# battery.net
KiCad netlist of a schematic drawn in Altium Designer
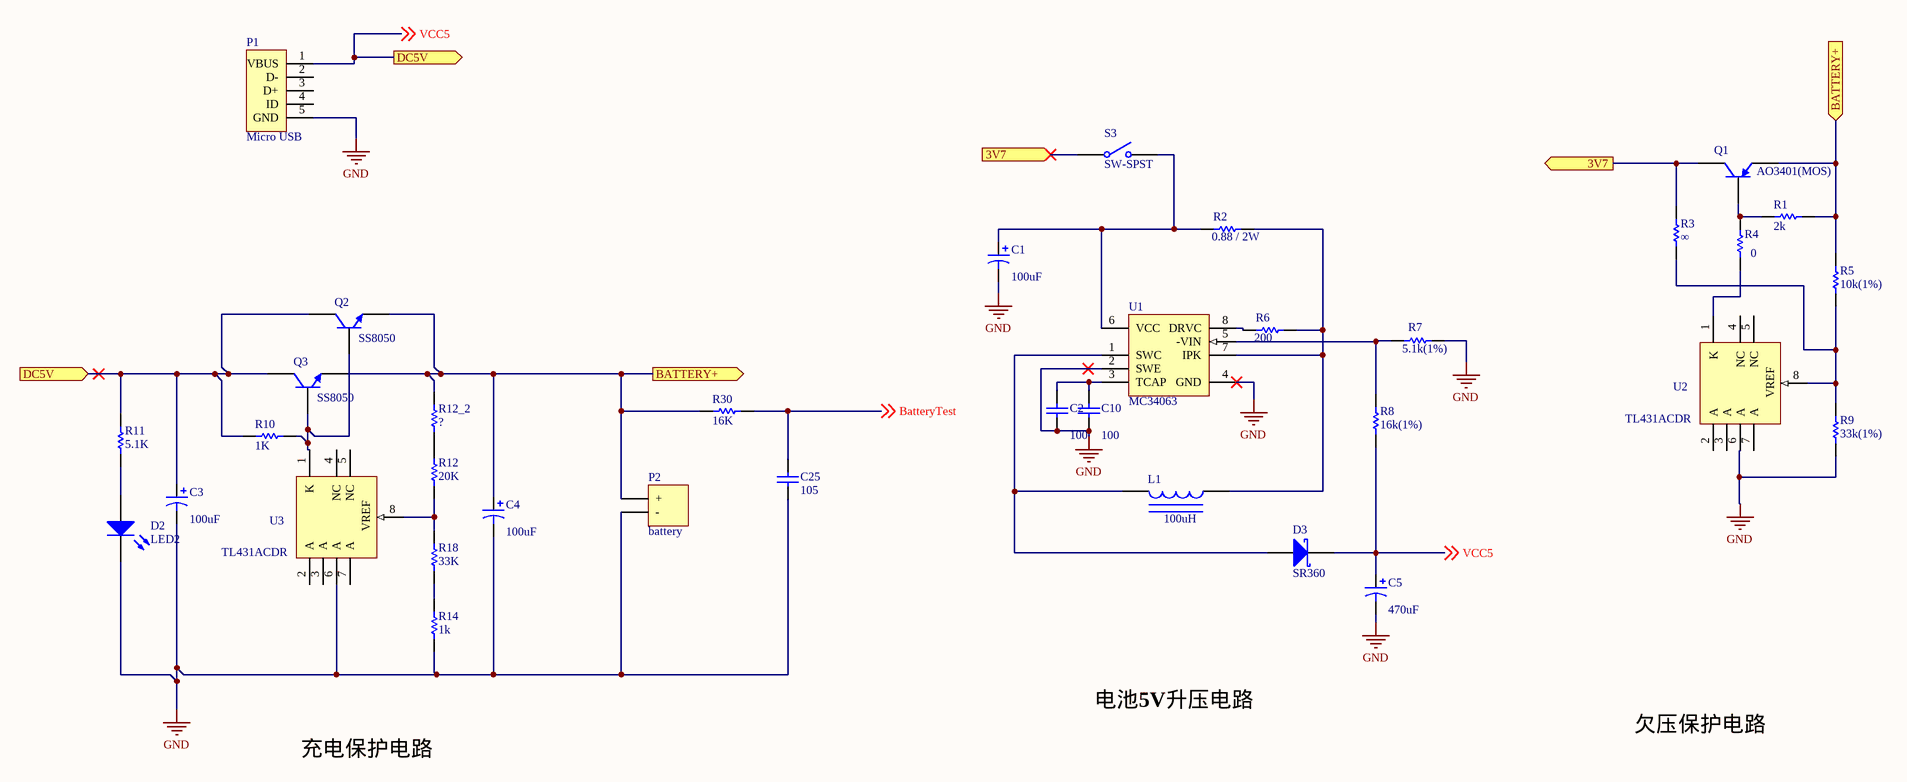
[diagram p0: battery.SchDoc]

(export (version "E")
  (design (tool "Eeschema 10.0.6"))
  (components
    (comp (ref "C1")
      (value "100uF")
      (footprint "cap_al")
      (description "Polarized Capacitor (Radial)")
      (fields (field (name "Comment") "Cap Pol1") (field (name "PUBLISHER") "Altium Limited"))
      (libsource (lib "Miscellaneous Devices") (part "Cap Pol1"))
    )
    (comp (ref "C2")
      (value "100")
      (footprint "C0805")
      (description "Capacitor")
      (fields (field (name "Comment") "Cap") (field (name "PUBLISHER") "Altium Limited"))
      (libsource (lib "Miscellaneous Devices") (part "Cap"))
    )
    (comp (ref "C3")
      (value "100uF")
      (footprint "cap_al")
      (description "Polarized Capacitor (Radial)")
      (fields (field (name "Comment") "Cap Pol1") (field (name "PUBLISHER") "Altium Limited"))
      (libsource (lib "Miscellaneous Devices") (part "Cap Pol1"))
    )
    (comp (ref "C4")
      (value "100uF")
      (footprint "cap_al")
      (description "Polarized Capacitor (Radial)")
      (fields (field (name "Comment") "Cap Pol1") (field (name "PUBLISHER") "Altium Limited"))
      (libsource (lib "Miscellaneous Devices") (part "Cap Pol1"))
    )
    (comp (ref "C5")
      (value "470uF")
      (footprint "CD5")
      (description "Polarized Capacitor (Radial)")
      (fields (field (name "Comment") "Cap Pol1") (field (name "PUBLISHER") "Altium Limited"))
      (libsource (lib "Miscellaneous Devices") (part "Cap Pol1"))
    )
    (comp (ref "C10")
      (value "100")
      (footprint "C0805")
      (description "Capacitor")
      (fields (field (name "Comment") "Cap") (field (name "PUBLISHER") "Altium Limited"))
      (libsource (lib "Miscellaneous Devices") (part "Cap"))
    )
    (comp (ref "C25")
      (value "105")
      (footprint "C0805")
      (description "Capacitor")
      (fields (field (name "Comment") "Cap") (field (name "PUBLISHER") "Altium Limited"))
      (libsource (lib "Miscellaneous Devices") (part "Cap"))
    )
    (comp (ref "D2")
      (value "LED2")
      (footprint "HDR1X2")
      (description "Typical RED, GREEN, YELLOW, AMBER GaAs LED")
      (fields (field (name "PUBLISHER") "Altium Limited"))
      (libsource (lib "Miscellaneous Devices") (part "LED2"))
    )
    (comp (ref "D3")
      (value "SR360")
      (footprint "SMB")
      (description "Schottky Diode")
      (fields (field (name "PUBLISHER") "Altium Limited"))
      (libsource (lib "Miscellaneous Devices") (part "D Schottky"))
    )
    (comp (ref "L1")
      (value "100uH")
      (footprint "INDC")
      (description "Magnetic-Core Inductor")
      (fields (field (name "Comment") "Inductor Iron") (field (name "PUBLISHER") "Altium Limited"))
      (libsource (lib "Miscellaneous Devices") (part "Inductor Iron"))
    )
    (comp (ref "P1")
      (value "Micro USB")
      (footprint "MICRO-USB")
      (description "Header, 5-Pin")
      (fields (field (name "PUBLISHER") "Altium Limited"))
      (libsource (lib "Miscellaneous Connectors") (part "Header 5"))
    )
    (comp (ref "P2")
      (value "battery")
      (footprint "HDR1X2")
      (description "Header, 2-Pin")
      (fields (field (name "PUBLISHER") "Altium Limited"))
      (libsource (lib "Miscellaneous Connectors") (part "Header 2"))
    )
    (comp (ref "Q1")
      (value "AO3401(MOS)")
      (footprint "SOT-23B_N")
      (description "PNP Bipolar Transistor")
      (fields (field (name "PUBLISHER") "Altium Limited"))
      (libsource (lib "Miscellaneous Devices") (part "PNP"))
    )
    (comp (ref "Q2")
      (value "SS8050")
      (footprint "SOT-23_N")
      (description "NPN Bipolar Transistor")
      (fields (field (name "PUBLISHER") "Altium Limited"))
      (libsource (lib "Miscellaneous Devices") (part "NPN"))
    )
    (comp (ref "Q3")
      (value "SS8050")
      (footprint "SOT-23_N")
      (description "NPN Bipolar Transistor")
      (fields (field (name "PUBLISHER") "Altium Limited"))
      (libsource (lib "Miscellaneous Devices") (part "NPN"))
    )
    (comp (ref "R1")
      (value "2k")
      (footprint "6-0805_N")
      (description "Resistor")
      (fields (field (name "Comment") "Res1") (field (name "PUBLISHER") "Altium Limited"))
      (libsource (lib "Miscellaneous Devices") (part "Res1"))
    )
    (comp (ref "R2")
      (value "0.88 / 2W")
      (footprint "AXIAL-0.8")
      (description "Resistor")
      (fields (field (name "Comment") "Res1") (field (name "PUBLISHER") "Altium Limited"))
      (libsource (lib "Miscellaneous Devices") (part "Res1"))
    )
    (comp (ref "R3")
      (value "∞")
      (footprint "6-0805_N")
      (description "Resistor")
      (fields (field (name "Comment") "Res1") (field (name "PUBLISHER") "Altium Limited"))
      (libsource (lib "Miscellaneous Devices") (part "Res1"))
    )
    (comp (ref "R4")
      (value "0")
      (footprint "6-0805_N")
      (description "Resistor")
      (fields (field (name "Comment") "Res1") (field (name "PUBLISHER") "Altium Limited"))
      (libsource (lib "Miscellaneous Devices") (part "Res1"))
    )
    (comp (ref "R5")
      (value "10k(1%)")
      (footprint "6-0805_N")
      (description "Resistor")
      (fields (field (name "Comment") "Res1") (field (name "PUBLISHER") "Altium Limited"))
      (libsource (lib "Miscellaneous Devices") (part "Res1"))
    )
    (comp (ref "R6")
      (value "200")
      (footprint "6-0805_N")
      (description "Resistor")
      (fields (field (name "Comment") "Res1") (field (name "PUBLISHER") "Altium Limited"))
      (libsource (lib "Miscellaneous Devices") (part "Res1"))
    )
    (comp (ref "R7")
      (value "5.1k(1%)")
      (footprint "6-0805_N")
      (description "Resistor")
      (fields (field (name "Comment") "Res1") (field (name "PUBLISHER") "Altium Limited"))
      (libsource (lib "Miscellaneous Devices") (part "Res1"))
    )
    (comp (ref "R8")
      (value "16k(1%)")
      (footprint "6-0805_N")
      (description "Resistor")
      (fields (field (name "Comment") "Res1") (field (name "PUBLISHER") "Altium Limited"))
      (libsource (lib "Miscellaneous Devices") (part "Res1"))
    )
    (comp (ref "R9")
      (value "33k(1%)")
      (footprint "6-0805_N")
      (description "Resistor")
      (fields (field (name "Comment") "Res1") (field (name "PUBLISHER") "Altium Limited"))
      (libsource (lib "Miscellaneous Devices") (part "Res1"))
    )
    (comp (ref "R10")
      (value "1K")
      (footprint "6-0805_N")
      (description "Resistor")
      (fields (field (name "Comment") "Res1") (field (name "PUBLISHER") "Altium Limited"))
      (libsource (lib "Miscellaneous Devices") (part "Res1"))
    )
    (comp (ref "R11")
      (value "5.1K")
      (footprint "6-0805_N")
      (description "Resistor")
      (fields (field (name "Comment") "Res1") (field (name "PUBLISHER") "Altium Limited"))
      (libsource (lib "Miscellaneous Devices") (part "Res1"))
    )
    (comp (ref "R12")
      (value "20K")
      (footprint "6-0805_N")
      (description "Resistor")
      (fields (field (name "Comment") "Res1") (field (name "PUBLISHER") "Altium Limited"))
      (libsource (lib "Miscellaneous Devices") (part "Res1"))
    )
    (comp (ref "R12_2")
      (value "?")
      (footprint "6-0805_N")
      (description "Resistor")
      (fields (field (name "Comment") "Res1") (field (name "PUBLISHER") "Altium Limited"))
      (libsource (lib "Miscellaneous Devices") (part "Res1"))
    )
    (comp (ref "R14")
      (value "1k")
      (footprint "6-0805_N")
      (description "Resistor")
      (fields (field (name "Comment") "Res1") (field (name "PUBLISHER") "Altium Limited"))
      (libsource (lib "Miscellaneous Devices") (part "Res1"))
    )
    (comp (ref "R18")
      (value "33K")
      (footprint "6-0805_N")
      (description "Resistor")
      (fields (field (name "Comment") "Res1") (field (name "PUBLISHER") "Altium Limited"))
      (libsource (lib "Miscellaneous Devices") (part "Res1"))
    )
    (comp (ref "R30")
      (value "16K")
      (footprint "6-0805_N")
      (description "Resistor")
      (fields (field (name "Comment") "Res1") (field (name "PUBLISHER") "Altium Limited"))
      (libsource (lib "Miscellaneous Devices") (part "Res1"))
    )
    (comp (ref "S3")
      (value "SW-SPST")
      (footprint "HDR1X2")
      (description "Single-Pole, Single-Throw Switch")
      (fields (field (name "PUBLISHER") "Altium Limited"))
      (libsource (lib "Miscellaneous Devices") (part "SW-SPST"))
    )
    (comp (ref "U1")
      (value "MC34063")
      (footprint "751-02_N")
      (description "DC-to-DC Converter Control Circuit")
      (fields (field (name "PUBLISHER") "Altium Limited"))
      (libsource (lib "Motorola Power Mgt DC-DC Converter") (part "MC34063AD"))
    )
    (comp (ref "U2")
      (value "TL431ACDR")
      (footprint "D008_N")
      (description "Adjustable Precision Shunt Regulator")
      (fields (field (name "PUBLISHER") "Altium Limited"))
      (libsource (lib "TI Power Mgt Voltage Regulator") (part "TL431ACDR"))
    )
    (comp (ref "U3")
      (value "TL431ACDR")
      (footprint "D008_N")
      (description "Adjustable Precision Shunt Regulator")
      (fields (field (name "PUBLISHER") "Altium Limited"))
      (libsource (lib "TI Power Mgt Voltage Regulator") (part "TL431ACDR"))
    )
  )
  (nets
    (net (code "1") (name "/3V7") (class "Default")
      (node (ref "Q1") (pin "1") (pinfunction "C_1") (pintype "passive"))
      (node (ref "R3") (pin "2") (pinfunction "2_2") (pintype "passive"))
      (node (ref "S3") (pin "1") (pinfunction "COMMON_1") (pintype "passive"))
    )
    (net (code "2") (name "/BATTERY+") (class "Default")
      (node (ref "C4") (pin "1") (pinfunction "1_1") (pintype "passive"))
      (node (ref "P2") (pin "1") (pinfunction "+_1") (pintype "passive"))
      (node (ref "Q1") (pin "3") (pinfunction "E_3") (pintype "passive"))
      (node (ref "Q2") (pin "3") (pinfunction "E_3") (pintype "passive"))
      (node (ref "Q3") (pin "3") (pinfunction "E_3") (pintype "passive"))
      (node (ref "R1") (pin "1") (pinfunction "1_1") (pintype "passive"))
      (node (ref "R12_2") (pin "1") (pinfunction "1_1") (pintype "passive"))
      (node (ref "R30") (pin "2") (pinfunction "2_2") (pintype "passive"))
      (node (ref "R5") (pin "2") (pinfunction "2_2") (pintype "passive"))
    )
    (net (code "3") (name "BatteryTest") (class "Default")
      (node (ref "C25") (pin "2") (pinfunction "2_2") (pintype "passive"))
      (node (ref "R30") (pin "1") (pinfunction "1_1") (pintype "passive"))
    )
    (net (code "4") (name "GND") (class "Default")
      (node (ref "C1") (pin "2") (pinfunction "2_2") (pintype "passive"))
      (node (ref "C10") (pin "1") (pinfunction "1_1") (pintype "passive"))
      (node (ref "C2") (pin "1") (pinfunction "1_1") (pintype "passive"))
      (node (ref "C25") (pin "1") (pinfunction "1_1") (pintype "passive"))
      (node (ref "C3") (pin "2") (pinfunction "2_2") (pintype "passive"))
      (node (ref "C4") (pin "2") (pinfunction "2_2") (pintype "passive"))
      (node (ref "C5") (pin "2") (pinfunction "2_2") (pintype "passive"))
      (node (ref "D2") (pin "2") (pinfunction "K_2") (pintype "passive"))
      (node (ref "P1") (pin "5") (pinfunction "GND_5") (pintype "passive"))
      (node (ref "P2") (pin "2") (pinfunction "-_2") (pintype "passive"))
      (node (ref "R14") (pin "2") (pinfunction "2_2") (pintype "passive"))
      (node (ref "R7") (pin "2") (pinfunction "2_2") (pintype "passive"))
      (node (ref "R9") (pin "1") (pinfunction "1_1") (pintype "passive"))
      (node (ref "U1") (pin "2") (pinfunction "SWE_2") (pintype "open_emitter"))
      (node (ref "U1") (pin "4") (pinfunction "GND_4") (pintype "power_in"))
      (node (ref "U2") (pin "6") (pinfunction "A_6") (pintype "power_in"))
      (node (ref "U3") (pin "6") (pinfunction "A_6") (pintype "power_in"))
    )
    (net (code "5") (name "Net-(D2-A)") (class "Default")
      (node (ref "D2") (pin "1") (pinfunction "A_1") (pintype "passive"))
      (node (ref "R11") (pin "2") (pinfunction "2_2") (pintype "passive"))
    )
    (net (code "6") (name "Net-(D3-A)") (class "Default")
      (node (ref "D3") (pin "1") (pinfunction "A_1") (pintype "passive"))
      (node (ref "L1") (pin "2") (pinfunction "2_2") (pintype "passive"))
      (node (ref "U1") (pin "1") (pinfunction "SWC_1") (pintype "open_collector"))
    )
    (net (code "7") (name "Net-(Q1-B)") (class "Default")
      (node (ref "Q1") (pin "2") (pinfunction "B_2") (pintype "passive"))
      (node (ref "R1") (pin "2") (pinfunction "2_2") (pintype "passive"))
      (node (ref "R4") (pin "2") (pinfunction "2_2") (pintype "passive"))
    )
    (net (code "8") (name "Net-(Q2-B)") (class "Default")
      (node (ref "Q2") (pin "2") (pinfunction "B_2") (pintype "passive"))
      (node (ref "Q3") (pin "2") (pinfunction "B_2") (pintype "passive"))
      (node (ref "R10") (pin "1") (pinfunction "1_1") (pintype "passive"))
      (node (ref "U3") (pin "1") (pinfunction "K_1") (pintype "power_in"))
    )
    (net (code "9") (name "Net-(R12-Pad1)") (class "Default")
      (node (ref "R12") (pin "1") (pinfunction "1_1") (pintype "passive"))
      (node (ref "R12_2") (pin "2") (pinfunction "2_2") (pintype "passive"))
    )
    (net (code "10") (name "Net-(R14-Pad1)") (class "Default")
      (node (ref "R14") (pin "1") (pinfunction "1_1") (pintype "passive"))
      (node (ref "R18") (pin "2") (pinfunction "2_2") (pintype "passive"))
    )
    (net (code "11") (name "Net-(S3-NO)") (class "Default")
      (node (ref "C1") (pin "1") (pinfunction "1_1") (pintype "passive"))
      (node (ref "R2") (pin "1") (pinfunction "1_1") (pintype "passive"))
      (node (ref "S3") (pin "2") (pinfunction "NO_2") (pintype "passive"))
      (node (ref "U1") (pin "6") (pinfunction "VCC_6") (pintype "power_in"))
    )
    (net (code "12") (name "Net-(U1--VIN)") (class "Default")
      (node (ref "R7") (pin "1") (pinfunction "1_1") (pintype "passive"))
      (node (ref "R8") (pin "2") (pinfunction "2_2") (pintype "passive"))
      (node (ref "U1") (pin "5") (pinfunction "-VIN_5") (pintype "input"))
    )
    (net (code "13") (name "Net-(U1-DRVC)") (class "Default")
      (node (ref "R6") (pin "1") (pinfunction "1_1") (pintype "passive"))
      (node (ref "U1") (pin "8") (pinfunction "DRVC_8") (pintype "open_collector"))
    )
    (net (code "14") (name "Net-(U1-IPK)") (class "Default")
      (node (ref "L1") (pin "1") (pinfunction "1_1") (pintype "passive"))
      (node (ref "R2") (pin "2") (pinfunction "2_2") (pintype "passive"))
      (node (ref "R6") (pin "2") (pinfunction "2_2") (pintype "passive"))
      (node (ref "U1") (pin "7") (pinfunction "IPK_7") (pintype "passive"))
    )
    (net (code "15") (name "Net-(U1-TCAP)") (class "Default")
      (node (ref "C10") (pin "2") (pinfunction "2_2") (pintype "passive"))
      (node (ref "C2") (pin "2") (pinfunction "2_2") (pintype "passive"))
      (node (ref "U1") (pin "3") (pinfunction "TCAP_3") (pintype "passive"))
    )
    (net (code "16") (name "Net-(U2-K)") (class "Default")
      (node (ref "R4") (pin "1") (pinfunction "1_1") (pintype "passive"))
      (node (ref "U2") (pin "1") (pinfunction "K_1") (pintype "power_in"))
    )
    (net (code "17") (name "Net-(U2-VREF)") (class "Default")
      (node (ref "R3") (pin "1") (pinfunction "1_1") (pintype "passive"))
      (node (ref "R5") (pin "1") (pinfunction "1_1") (pintype "passive"))
      (node (ref "R9") (pin "2") (pinfunction "2_2") (pintype "passive"))
      (node (ref "U2") (pin "8") (pinfunction "VREF_8") (pintype "input"))
    )
    (net (code "18") (name "Net-(U3-VREF)") (class "Default")
      (node (ref "R12") (pin "2") (pinfunction "2_2") (pintype "passive"))
      (node (ref "R18") (pin "1") (pinfunction "1_1") (pintype "passive"))
      (node (ref "U3") (pin "8") (pinfunction "VREF_8") (pintype "input"))
    )
    (net (code "19") (name "VCC5") (class "Default")
      (node (ref "C3") (pin "1") (pinfunction "1_1") (pintype "passive"))
      (node (ref "C5") (pin "1") (pinfunction "1_1") (pintype "passive"))
      (node (ref "D3") (pin "2") (pinfunction "K_2") (pintype "passive"))
      (node (ref "P1") (pin "1") (pinfunction "VBUS_1") (pintype "passive"))
      (node (ref "Q2") (pin "1") (pinfunction "C_1") (pintype "passive"))
      (node (ref "Q3") (pin "1") (pinfunction "C_1") (pintype "passive"))
      (node (ref "R10") (pin "2") (pinfunction "2_2") (pintype "passive"))
      (node (ref "R11") (pin "1") (pinfunction "1_1") (pintype "passive"))
      (node (ref "R8") (pin "1") (pinfunction "1_1") (pintype "passive"))
    )
    (net (code "20") (name "unconnected-(P1-D+-Pad3)") (class "Default")
      (node (ref "P1") (pin "3") (pinfunction "D+_3") (pintype "passive"))
    )
    (net (code "21") (name "unconnected-(P1-D--Pad2)") (class "Default")
      (node (ref "P1") (pin "2") (pinfunction "D-_2") (pintype "passive"))
    )
    (net (code "22") (name "unconnected-(P1-ID-Pad4)") (class "Default")
      (node (ref "P1") (pin "4") (pinfunction "ID_4") (pintype "passive"))
    )
    (net (code "23") (name "unconnected-(U2-A-Pad2)") (class "Default")
      (node (ref "U2") (pin "2") (pinfunction "A_2") (pintype "power_in"))
    )
    (net (code "24") (name "unconnected-(U2-A-Pad3)") (class "Default")
      (node (ref "U2") (pin "3") (pinfunction "A_3") (pintype "power_in"))
    )
    (net (code "25") (name "unconnected-(U2-A-Pad7)") (class "Default")
      (node (ref "U2") (pin "7") (pinfunction "A_7") (pintype "power_in"))
    )
    (net (code "26") (name "unconnected-(U2-NC-Pad4)") (class "Default")
      (node (ref "U2") (pin "4") (pinfunction "NC_4") (pintype "passive"))
    )
    (net (code "27") (name "unconnected-(U2-NC-Pad5)") (class "Default")
      (node (ref "U2") (pin "5") (pinfunction "NC_5") (pintype "passive"))
    )
    (net (code "28") (name "unconnected-(U3-A-Pad2)") (class "Default")
      (node (ref "U3") (pin "2") (pinfunction "A_2") (pintype "power_in"))
    )
    (net (code "29") (name "unconnected-(U3-A-Pad3)") (class "Default")
      (node (ref "U3") (pin "3") (pinfunction "A_3") (pintype "power_in"))
    )
    (net (code "30") (name "unconnected-(U3-A-Pad7)") (class "Default")
      (node (ref "U3") (pin "7") (pinfunction "A_7") (pintype "power_in"))
    )
    (net (code "31") (name "unconnected-(U3-NC-Pad4)") (class "Default")
      (node (ref "U3") (pin "4") (pinfunction "NC_4") (pintype "passive"))
    )
    (net (code "32") (name "unconnected-(U3-NC-Pad5)") (class "Default")
      (node (ref "U3") (pin "5") (pinfunction "NC_5") (pintype "passive"))
    )
  )
)
